# nrf91-feather.net
KiCad netlist of a schematic drawn in EAGLE
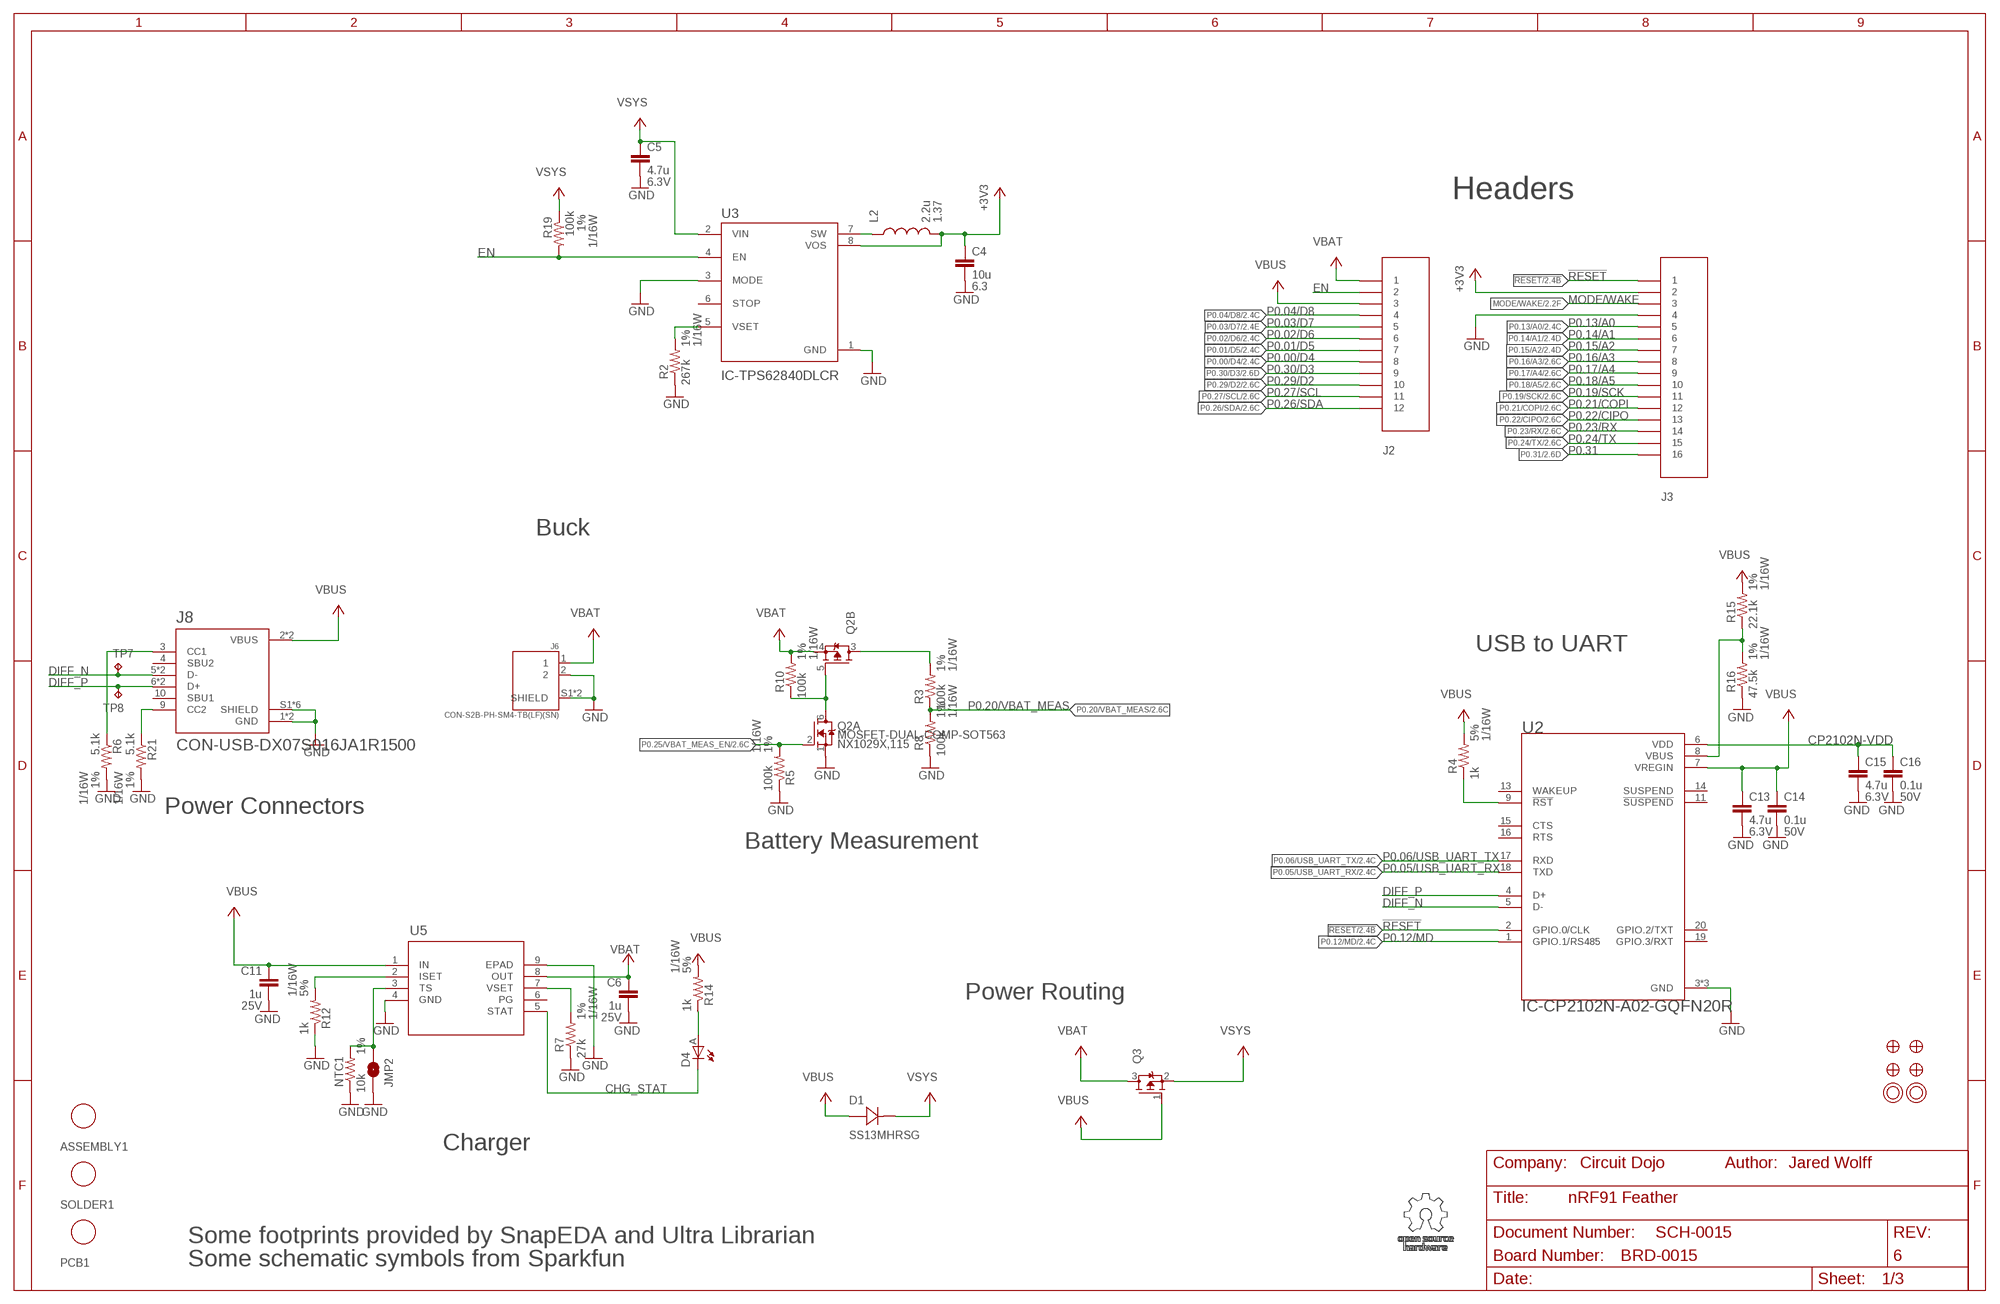
[diagram p0: schematic, sheet 1]
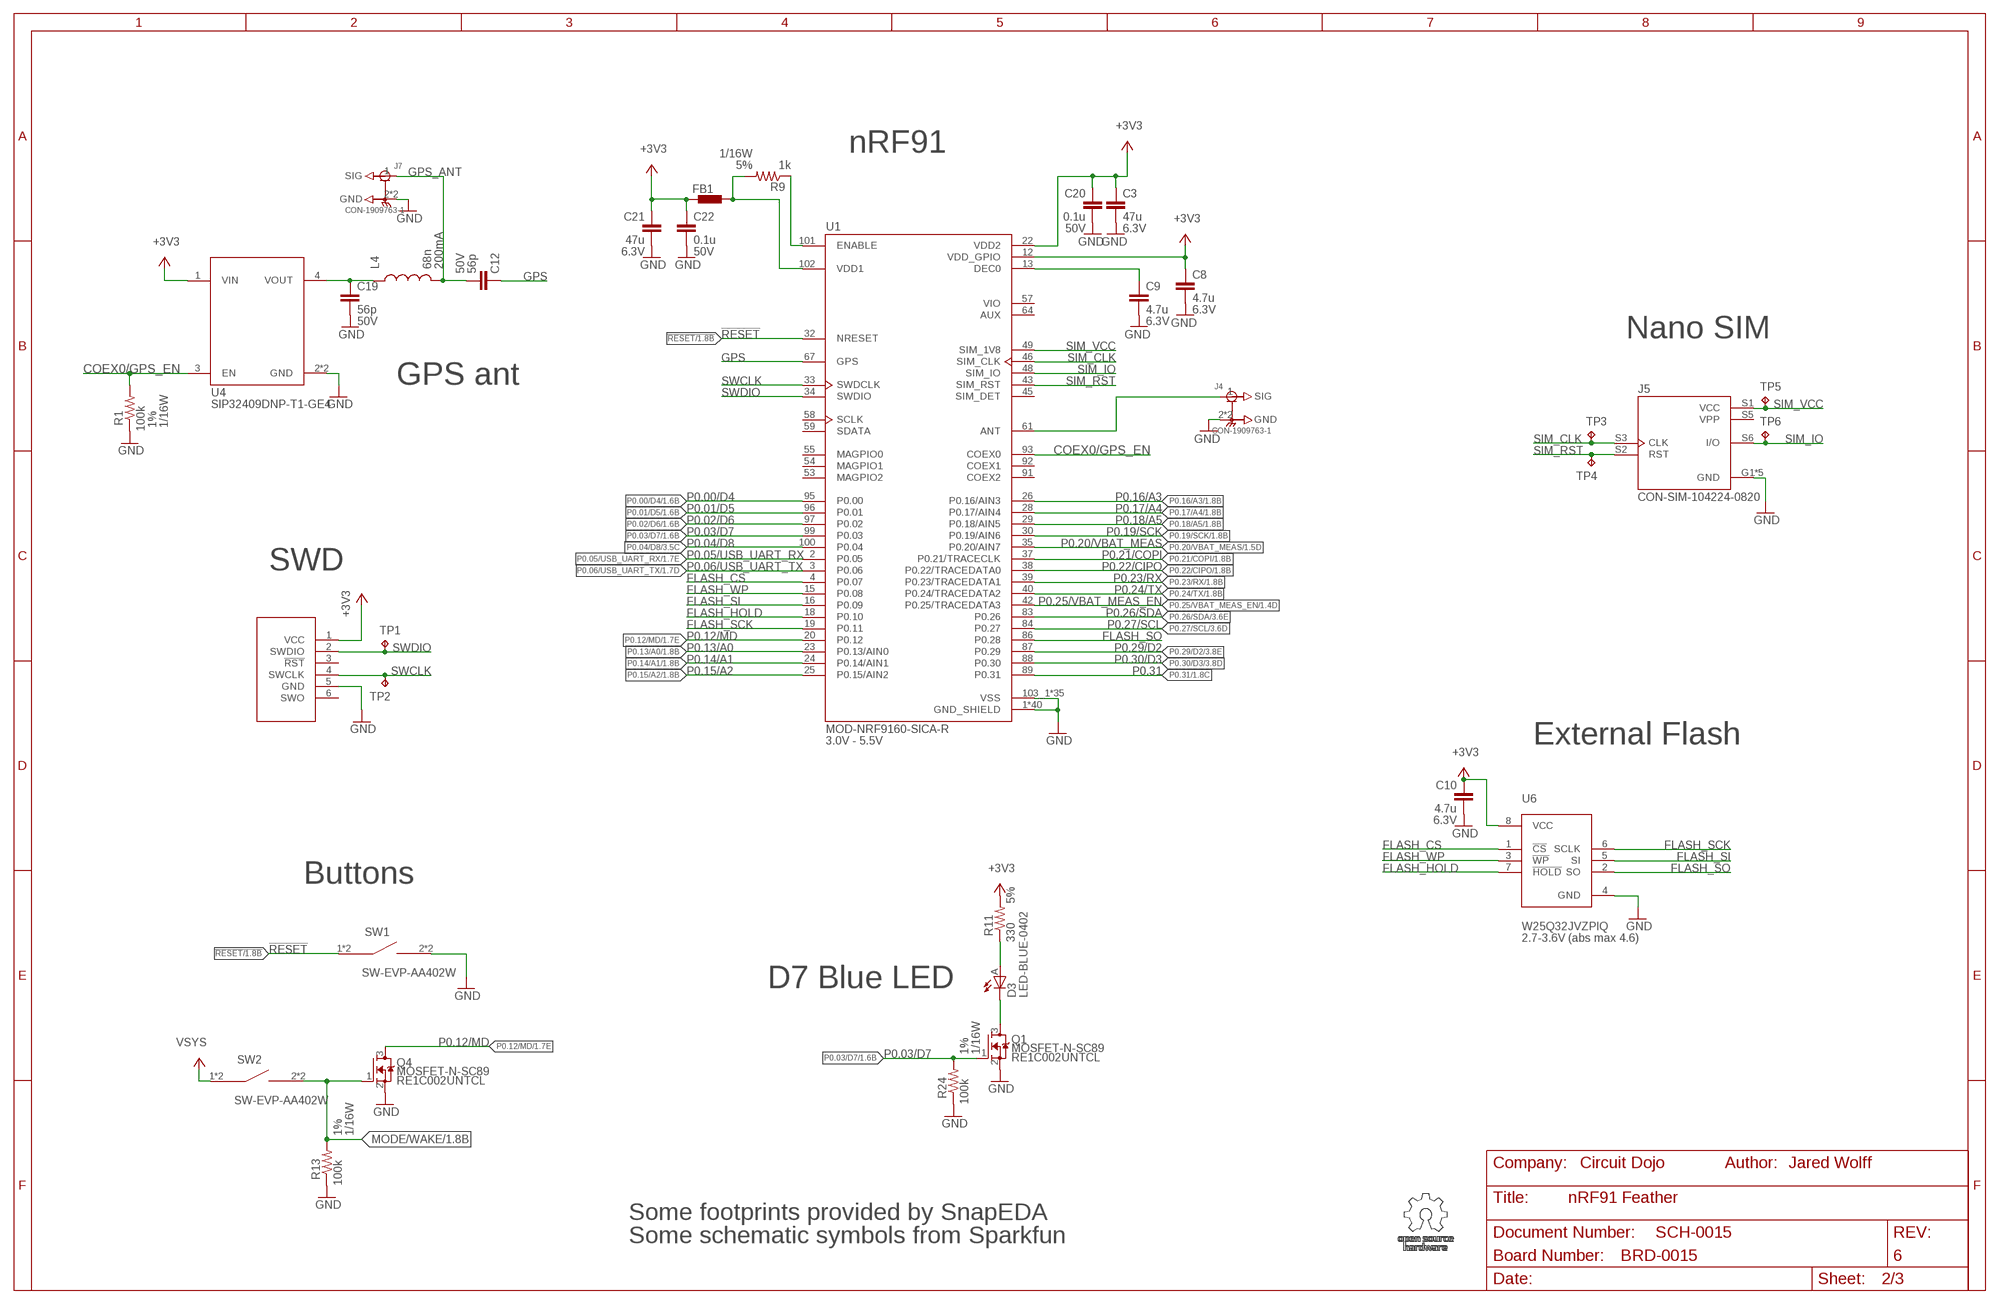
[diagram p1: schematic, sheet 2]
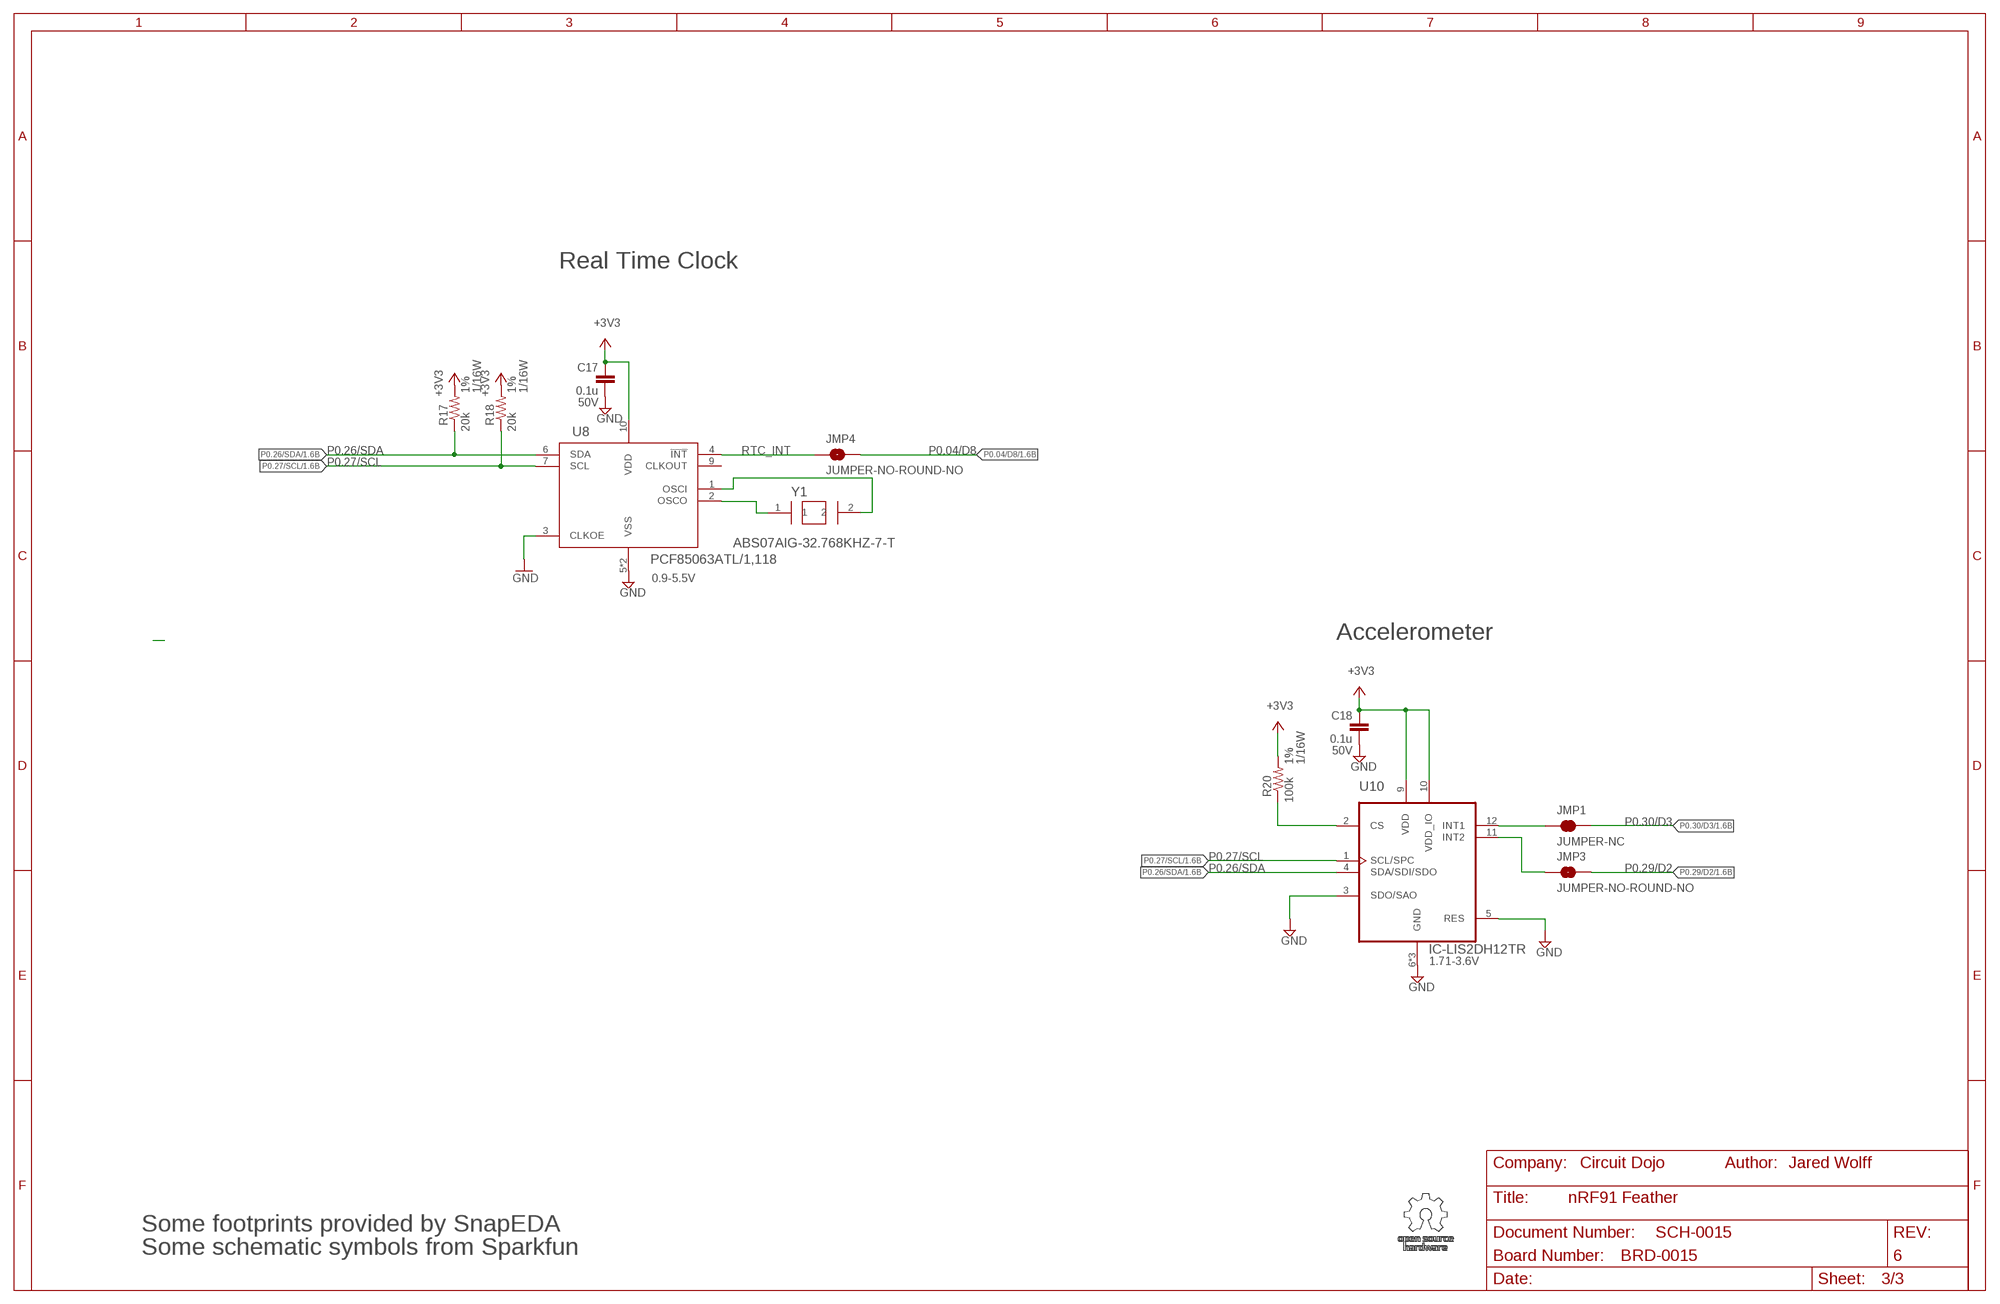
[diagram p2: schematic, sheet 3]

(export (version "E")
  (design (tool "Eeschema 10.0.6"))
  (components
    (comp (ref "ASSEMBLY1")
      (value "ASSY-COST-NRF91-FEATHER")
      (footprint "eagle-import:PLACEHOLDER")
      (fields (field (name "MPN") "ASSY-COST-NRF9160-FEATHER"))
      (libsource (lib "eagle-import") (part "ASSY-COST-NRF91-FEATHER"))
    )
    (comp (ref "C4")
      (value "10u")
      (footprint "eagle-import:C0603")
      (fields (field (name "MPN") "JMK107ABJ106MA-T") (field (name "VOLTHIGH") "6.3"))
      (libsource (lib "eagle-import") (part "CAP-0603-10U-6.3V"))
    )
    (comp (ref "C5")
      (value "4.7u")
      (footprint "eagle-import:C0603")
      (fields (field (name "MPN") "JMK107BB7475MA-T") (field (name "VOLTHIGH") "6.3V"))
      (libsource (lib "eagle-import") (part "CAP-0603-4.7U-6.3V-2"))
    )
    (comp (ref "C6")
      (value "1u")
      (footprint "eagle-import:CAPC1005X55N")
      (fields
        (field (name "MF") "TDK")
        (field (name "MPN") "C1005X5R1E105M050BC")
        (field (name "VOLTHIGH") "25V")
      )
      (libsource (lib "eagle-import") (part "CAP-0402-1U-25V-1"))
    )
    (comp (ref "C11")
      (value "1u")
      (footprint "eagle-import:CAPC1005X55N")
      (fields
        (field (name "MF") "TDK")
        (field (name "MPN") "C1005X5R1E105M050BC")
        (field (name "VOLTHIGH") "25V")
      )
      (libsource (lib "eagle-import") (part "CAP-0402-1U-25V-1"))
    )
    (comp (ref "C13")
      (value "4.7u")
      (footprint "eagle-import:C0603")
      (fields (field (name "MPN") "JMK107BB7475MA-T") (field (name "VOLTHIGH") "6.3V"))
      (libsource (lib "eagle-import") (part "CAP-0603-4.7U-6.3V-2"))
    )
    (comp (ref "C14")
      (value "0.1u")
      (footprint "eagle-import:CAPC1005X55N")
      (fields
        (field (name "MF") "Taiyo Yuden")
        (field (name "MPN") "UMK105BJ104KV-F")
        (field (name "VOLTHIGH") "50V")
      )
      (libsource (lib "eagle-import") (part "CAP-0402-0.1U-50V"))
    )
    (comp (ref "C15")
      (value "4.7u")
      (footprint "eagle-import:C0603")
      (fields (field (name "MPN") "JMK107BB7475MA-T") (field (name "VOLTHIGH") "6.3V"))
      (libsource (lib "eagle-import") (part "CAP-0603-4.7U-6.3V-2"))
    )
    (comp (ref "C16")
      (value "0.1u")
      (footprint "eagle-import:CAPC1005X55N")
      (fields
        (field (name "MF") "Taiyo Yuden")
        (field (name "MPN") "UMK105BJ104KV-F")
        (field (name "VOLTHIGH") "50V")
      )
      (libsource (lib "eagle-import") (part "CAP-0402-0.1U-50V"))
    )
    (comp (ref "D1")
      (value "DIO-SCHOTTKY-1A-SMA-MICRO")
      (footprint "eagle-import:SMA-MICRO")
      (fields (field (name "MPN") "SS13MHRSG"))
      (libsource (lib "eagle-import") (part "DIO-SCHOTTKY-SMA-MICRO-1A"))
    )
    (comp (ref "D4")
      (value "LED-ORANGE-0402")
      (footprint "eagle-import:LED_EAST1005")
      (fields (field (name "MF") "Everlight Electronics Co Ltd") (field (name "MPN") "EAST1005GA1"))
      (libsource (lib "eagle-import") (part "LED-0402-ORANGE"))
    )
    (comp (ref "J2")
      (value "CON-HEADER-1X12-MALE-PIN")
      (footprint "eagle-import:CON-HEADER-1X12-MALE-PIN")
      (libsource (lib "eagle-import") (part "CON-HEADER-1X12-MALE-PIN"))
    )
    (comp (ref "J3")
      (value "CON-HEADER-1X16-MALE-PIN")
      (footprint "eagle-import:CON-HEADER-1X16-MALE-PIN")
      (libsource (lib "eagle-import") (part "CON-HEADER-1X16-MALE-PIN"))
    )
    (comp (ref "J6")
      (value "CON-S2B-PH-SM4-TB(LF)(SN)")
      (footprint "eagle-import:JST_S2B-PH-SM4-TB(LF)(SN)")
      (fields (field (name "MF") "JST Sales") (field (name "MPN") "S2B-PH-SM4-TB(LF)(SN)"))
      (libsource (lib "eagle-import") (part "CON-S2B-PH-SM4-TB(LF)(SN)"))
    )
    (comp (ref "J8")
      (value "CON-USB-DX07S016JA1R1500")
      (footprint "eagle-import:JAE_DX07S016JA1R1500")
      (fields
        (field (name "DIGI-KEY_PART_NUMBER") "670-DX07S016JA1R1500CT-ND")
        (field (name "MF") "JAE Electronics")
        (field (name "MP") "DX07S016JA1R1500")
      )
      (libsource (lib "eagle-import") (part "CON-USB-DX07S016JA1R1500"))
    )
    (comp (ref "JMP2")
      (value "JUMPER-NO-ROUND-NO")
      (footprint "eagle-import:JUMPER-ROUND-N0")
      (libsource (lib "eagle-import") (part "JUMPER-NO-ROUND-NO"))
    )
    (comp (ref "L2")
      (value "2.2u")
      (footprint "eagle-import:IND-2P0X2P0X1P2")
      (fields (field (name "CURRENT") "1.37") (field (name "MPN") "NRS2012T2R2MGJ"))
      (libsource (lib "eagle-import") (part "IND-2.2U-1.37A-2X2"))
    )
    (comp (ref "NTC1")
      (value "10k")
      (footprint "eagle-import:R0402-M")
      (fields
        (field (name "MF") "Murata Electronics")
        (field (name "MPN") "NCU15XH103F60RC")
        (field (name "TOLERANCE") "1%")
      )
      (libsource (lib "eagle-import") (part "NTC-0402-10K-1%"))
    )
    (comp (ref "PCB1")
      (value "PCB-NRF91-FEATHER")
      (footprint "eagle-import:PLACEHOLDER")
      (fields (field (name "MPN") "BRD-0015"))
      (libsource (lib "eagle-import") (part "PCB-NRF91-FEATHER"))
    )
    (comp (ref "Q2")
      (value "MOSFET-DUAL-COMP-SOT563")
      (footprint "eagle-import:SOT50P160X60-6N")
      (fields (field (name "MPN") "NX1029X,115"))
      (libsource (lib "eagle-import") (part "MOSFET-DUAL-COMP-SOT563"))
    )
    (comp (ref "Q3")
      (value "MOSFET-P-20V-4.7A-SOT23")
      (footprint "eagle-import:SOT23")
      (fields (field (name "MPN") "TSM500P02CX RFG"))
      (libsource (lib "eagle-import") (part "MOSFET-P-SOT23-20V-4.7A"))
    )
    (comp (ref "R2")
      (value "267k")
      (footprint "eagle-import:R0402-M")
      (fields
        (field (name "MPN") "RC0402FR-07267KL")
        (field (name "POWER") "1/16W")
        (field (name "TOLERANCE") "1%")
      )
      (libsource (lib "eagle-import") (part "RES-0402-267K-1%"))
    )
    (comp (ref "R3")
      (value "100k")
      (footprint "eagle-import:R0402-M")
      (fields
        (field (name "MPN") "RC0402FR07100KL")
        (field (name "POWER") "1/16W")
        (field (name "TOLERANCE") "1%")
      )
      (libsource (lib "eagle-import") (part "RES-0402-100K-1%"))
    )
    (comp (ref "R4")
      (value "1k")
      (footprint "eagle-import:R0402-M")
      (fields
        (field (name "MPN") "RC0402JR-071KL")
        (field (name "POWER") "1/16W")
        (field (name "TOLERANCE") "5%")
      )
      (libsource (lib "eagle-import") (part "RES-0402-1K-5%"))
    )
    (comp (ref "R5")
      (value "100k")
      (footprint "eagle-import:R0402-M")
      (fields
        (field (name "MPN") "RC0402FR07100KL")
        (field (name "POWER") "1/16W")
        (field (name "TOLERANCE") "1%")
      )
      (libsource (lib "eagle-import") (part "RES-0402-100K-1%"))
    )
    (comp (ref "R6")
      (value "5.1k")
      (footprint "eagle-import:R0402-M")
      (fields
        (field (name "MPN") "RC0402FR-075K1L")
        (field (name "POWER") "1/16W")
        (field (name "TOLERANCE") "1%")
      )
      (libsource (lib "eagle-import") (part "RES-0402-5.1K-1%"))
    )
    (comp (ref "R7")
      (value "27k")
      (footprint "eagle-import:R0402-M")
      (fields (field (name "MF") "Yageo") (field (name "POWER") "1/16W") (field (name "TOLERANCE") "1%"))
      (libsource (lib "eagle-import") (part "RES-0402-27K-1%"))
    )
    (comp (ref "R8")
      (value "100k")
      (footprint "eagle-import:R0402-M")
      (fields
        (field (name "MPN") "RC0402FR07100KL")
        (field (name "POWER") "1/16W")
        (field (name "TOLERANCE") "1%")
      )
      (libsource (lib "eagle-import") (part "RES-0402-100K-1%"))
    )
    (comp (ref "R10")
      (value "100k")
      (footprint "eagle-import:R0402-M")
      (fields
        (field (name "MPN") "RC0402FR07100KL")
        (field (name "POWER") "1/16W")
        (field (name "TOLERANCE") "1%")
      )
      (libsource (lib "eagle-import") (part "RES-0402-100K-1%"))
    )
    (comp (ref "R12")
      (value "1k")
      (footprint "eagle-import:R0402-M")
      (fields
        (field (name "MPN") "RC0402JR-071KL")
        (field (name "POWER") "1/16W")
        (field (name "TOLERANCE") "5%")
      )
      (libsource (lib "eagle-import") (part "RES-0402-1K-5%"))
    )
    (comp (ref "R14")
      (value "1k")
      (footprint "eagle-import:R0402-M")
      (fields
        (field (name "MPN") "RC0402JR-071KL")
        (field (name "POWER") "1/16W")
        (field (name "TOLERANCE") "5%")
      )
      (libsource (lib "eagle-import") (part "RES-0402-1K-5%"))
    )
    (comp (ref "R15")
      (value "22.1k")
      (footprint "eagle-import:R0402-M")
      (fields
        (field (name "MF") "Yageo")
        (field (name "MPN") "RC0402FR-0722K1L")
        (field (name "POWER") "1/16W")
        (field (name "TOLERANCE") "1%")
      )
      (libsource (lib "eagle-import") (part "RES-0402-22.1K-1%"))
    )
    (comp (ref "R16")
      (value "47.5k")
      (footprint "eagle-import:R0402-M")
      (fields
        (field (name "MF") "Yageo")
        (field (name "MPN") "RC0402FR-0747K5L")
        (field (name "POWER") "1/16W")
        (field (name "TOLERANCE") "1%")
      )
      (libsource (lib "eagle-import") (part "RES-0402-47.5K-1%"))
    )
    (comp (ref "R19")
      (value "100k")
      (footprint "eagle-import:R0402-M")
      (fields
        (field (name "MPN") "RC0402FR07100KL")
        (field (name "POWER") "1/16W")
        (field (name "TOLERANCE") "1%")
      )
      (libsource (lib "eagle-import") (part "RES-0402-100K-1%"))
    )
    (comp (ref "R21")
      (value "5.1k")
      (footprint "eagle-import:R0402-M")
      (fields
        (field (name "MPN") "RC0402FR-075K1L")
        (field (name "POWER") "1/16W")
        (field (name "TOLERANCE") "1%")
      )
      (libsource (lib "eagle-import") (part "RES-0402-5.1K-1%"))
    )
    (comp (ref "SOLDER1")
      (value "SOLDER-PASTE-ROOM-TEMP-50G")
      (footprint "eagle-import:PLACEHOLDER")
      (fields (field (name "MPN") "TS391SNL50") (field (name "MQTY") "150"))
      (libsource (lib "eagle-import") (part "SOLDER-PASTE-ROOM-TEMP-50G"))
    )
    (comp (ref "TP7")
      (value "TP-1SIDE-1P0")
      (footprint "eagle-import:TP-1P0")
      (libsource (lib "eagle-import") (part "TP-1SIDE-1P0"))
    )
    (comp (ref "TP8")
      (value "TP-1SIDE-1P0")
      (footprint "eagle-import:TP-1P0")
      (libsource (lib "eagle-import") (part "TP-1SIDE-1P0"))
    )
    (comp (ref "U$3")
      (value "FIDUCIAL-1MM")
      (footprint "eagle-import:FIDUCIAL-1MM")
      (libsource (lib "eagle-import") (part "FIDUCIAL-1MM"))
    )
    (comp (ref "U$4")
      (value "FIDUCIAL-1MM")
      (footprint "eagle-import:FIDUCIAL-1MM")
      (libsource (lib "eagle-import") (part "FIDUCIAL-1MM"))
    )
    (comp (ref "U$31")
      (value "MOUNTING-HOLE-2.5MM-PLATED")
      (footprint "eagle-import:MOUNTING-HOLE-2.5MM-PLATED")
      (libsource (lib "eagle-import") (part "MOUNTING-HOLE-2.5MM-PLATED"))
    )
    (comp (ref "U$32")
      (value "MOUNTING-HOLE-2.5MM-PLATED")
      (footprint "eagle-import:MOUNTING-HOLE-2.5MM-PLATED")
      (libsource (lib "eagle-import") (part "MOUNTING-HOLE-2.5MM-PLATED"))
    )
    (comp (ref "U$34")
      (value "FIDUCIAL-1MM")
      (footprint "eagle-import:FIDUCIAL-1MM")
      (libsource (lib "eagle-import") (part "FIDUCIAL-1MM"))
    )
    (comp (ref "U$35")
      (value "FIDUCIAL-1MM")
      (footprint "eagle-import:FIDUCIAL-1MM")
      (libsource (lib "eagle-import") (part "FIDUCIAL-1MM"))
    )
    (comp (ref "U2")
      (value "IC-CP2102N-A02-GQFN20R")
      (footprint "eagle-import:SILABS_CP2102N-A02-GQFN20R")
      (fields (field (name "MPN") "CP2102N-A02-GQFN20R") (field (name "MF") "Silicon Labs"))
      (libsource (lib "eagle-import") (part "IC-CP2102N-A02-GQFN20R"))
    )
    (comp (ref "U3")
      (value "IC-TPS62840DLCR")
      (footprint "eagle-import:SON50P200X150X100-8N")
      (fields (field (name "MF") "Texas Instruments") (field (name "MP") "TPS62840DLCR"))
      (libsource (lib "eagle-import") (part "IC-TPS62840DLCR"))
    )
    (comp (ref "U5")
      (value "IC-BQ25170JDSGR-WSON8")
      (footprint "eagle-import:WSON8_BQ2517_TEX-L")
      (fields
        (field (name "MF") "Texas Instruments")
        (field (name "MPN") "BQ25170JDSGR")
        (field (name "COPYRIGHT") "Copyright (C) 2022 Ultra Librarian. All rights reserved.")
      )
      (libsource (lib "eagle-import") (part "IC-BQ25170JDSGR-WSON8"))
    )
    (comp (ref "C17")
      (value "0.1u")
      (footprint "eagle-import:CAPC1005X55N")
      (fields
        (field (name "MF") "Taiyo Yuden")
        (field (name "MPN") "UMK105BJ104KV-F")
        (field (name "VOLTHIGH") "50V")
      )
      (libsource (lib "eagle-import") (part "CAP-0402-0.1U-50V"))
    )
    (comp (ref "C18")
      (value "0.1u")
      (footprint "eagle-import:CAPC1005X55N")
      (fields
        (field (name "MF") "Taiyo Yuden")
        (field (name "MPN") "UMK105BJ104KV-F")
        (field (name "VOLTHIGH") "50V")
      )
      (libsource (lib "eagle-import") (part "CAP-0402-0.1U-50V"))
    )
    (comp (ref "JMP1")
      (value "JUMPER-NC")
      (footprint "eagle-import:JUMPER-ROUND-NC")
      (libsource (lib "eagle-import") (part "JUMPER-NC"))
    )
    (comp (ref "JMP3")
      (value "JUMPER-NO-ROUND-NO")
      (footprint "eagle-import:JUMPER-ROUND-N0")
      (libsource (lib "eagle-import") (part "JUMPER-NO-ROUND-NO"))
    )
    (comp (ref "JMP4")
      (value "JUMPER-NO-ROUND-NO")
      (footprint "eagle-import:JUMPER-ROUND-N0")
      (libsource (lib "eagle-import") (part "JUMPER-NO-ROUND-NO"))
    )
    (comp (ref "R17")
      (value "20k")
      (footprint "eagle-import:R0402-M")
      (fields
        (field (name "MF") "Yageo")
        (field (name "MPN") "RC0402FR-0720KL")
        (field (name "POWER") "1/16W")
        (field (name "TOLERANCE") "1%")
      )
      (libsource (lib "eagle-import") (part "RES-0402-20K-1%"))
    )
    (comp (ref "R18")
      (value "20k")
      (footprint "eagle-import:R0402-M")
      (fields
        (field (name "MF") "Yageo")
        (field (name "MPN") "RC0402FR-0720KL")
        (field (name "POWER") "1/16W")
        (field (name "TOLERANCE") "1%")
      )
      (libsource (lib "eagle-import") (part "RES-0402-20K-1%"))
    )
    (comp (ref "R20")
      (value "100k")
      (footprint "eagle-import:R0402-M")
      (fields
        (field (name "MPN") "RC0402FR07100KL")
        (field (name "POWER") "1/16W")
        (field (name "TOLERANCE") "1%")
      )
      (libsource (lib "eagle-import") (part "RES-0402-100K-1%"))
    )
    (comp (ref "U8")
      (value "IC-PCF85063ATL/1")
      (footprint "eagle-import:DFN10_2P7X2P7-L")
      (fields (field (name "MPN") "PCF85063ATL/1,118") (field (name "MF") "NXP"))
      (libsource (lib "eagle-import") (part "IC-PCF85063ATL/1"))
    )
    (comp (ref "U10")
      (value "IC-LIS2DH12TR")
      (footprint "eagle-import:PQFN50P200X200100-12N")
      (fields (field (name "MF") "STMicroelectronics") (field (name "MPN") "LIS2DH12TR"))
      (libsource (lib "eagle-import") (part "IC-LIS2DH12TR"))
    )
    (comp (ref "Y1")
      (value "XTAL-ABS07AIG-32.768KHZ-7-T")
      (footprint "eagle-import:XTAL320X150X90")
      (fields (field (name "MPN") "ABS07AIG-32.768KHZ-7-T") (field (name "MF") "Abracon"))
      (libsource (lib "eagle-import") (part "XTAL-ABS07AIG-32.768KHZ-7-T"))
    )
    (comp (ref "C3")
      (value "47u")
      (footprint "eagle-import:C0805")
      (fields (field (name "MPN") "JMK212BJ476MG-T") (field (name "VOLTHIGH") "6.3V"))
      (libsource (lib "eagle-import") (part "CAP-0805-47U-6.3V"))
    )
    (comp (ref "C8")
      (value "4.7u")
      (footprint "eagle-import:C0603")
      (fields (field (name "MPN") "JMK107BB7475MA-T") (field (name "VOLTHIGH") "6.3V"))
      (libsource (lib "eagle-import") (part "CAP-0603-4.7U-6.3V-2"))
    )
    (comp (ref "C9")
      (value "4.7u")
      (footprint "eagle-import:C0603")
      (fields (field (name "MPN") "JMK107BB7475MA-T") (field (name "VOLTHIGH") "6.3V"))
      (libsource (lib "eagle-import") (part "CAP-0603-4.7U-6.3V-2"))
    )
    (comp (ref "C10")
      (value "4.7u")
      (footprint "eagle-import:C0603")
      (fields (field (name "MPN") "JMK107BB7475MA-T") (field (name "VOLTHIGH") "6.3V"))
      (libsource (lib "eagle-import") (part "CAP-0603-4.7U-6.3V-2"))
    )
    (comp (ref "C12")
      (value "56p")
      (footprint "eagle-import:CAPC1005X55N")
      (fields
        (field (name "MF") "Yageo")
        (field (name "MPN") "CC0402GRNPO9BN560")
        (field (name "VOLTHIGH") "50V")
      )
      (libsource (lib "eagle-import") (part "CAP-0402-56PF-50V-1"))
    )
    (comp (ref "C19")
      (value "56p")
      (footprint "eagle-import:CAPC1005X55N")
      (fields
        (field (name "MF") "Yageo")
        (field (name "MPN") "CC0402GRNPO9BN560")
        (field (name "VOLTHIGH") "50V")
      )
      (libsource (lib "eagle-import") (part "CAP-0402-56PF-50V-1"))
    )
    (comp (ref "C20")
      (value "0.1u")
      (footprint "eagle-import:CAPC1005X55N")
      (fields
        (field (name "MF") "Taiyo Yuden")
        (field (name "MPN") "UMK105BJ104KV-F")
        (field (name "VOLTHIGH") "50V")
      )
      (libsource (lib "eagle-import") (part "CAP-0402-0.1U-50V"))
    )
    (comp (ref "C21")
      (value "47u")
      (footprint "eagle-import:C0805")
      (fields (field (name "MPN") "JMK212BJ476MG-T") (field (name "VOLTHIGH") "6.3V"))
      (libsource (lib "eagle-import") (part "CAP-0805-47U-6.3V"))
    )
    (comp (ref "C22")
      (value "0.1u")
      (footprint "eagle-import:CAPC1005X55N")
      (fields
        (field (name "MF") "Taiyo Yuden")
        (field (name "MPN") "UMK105BJ104KV-F")
        (field (name "VOLTHIGH") "50V")
      )
      (libsource (lib "eagle-import") (part "CAP-0402-0.1U-50V"))
    )
    (comp (ref "D3")
      (value "LED-BLUE-0402")
      (footprint "eagle-import:LED_EAST1005")
      (fields (field (name "MF") "Everlight Electronics Co Ltd") (field (name "MPN") "EAST10052BA0"))
      (libsource (lib "eagle-import") (part "LED-0402-BLUE"))
    )
    (comp (ref "FB1")
      (value "FERRITE-120-100MHZ-0402")
      (footprint "eagle-import:R0402-M")
      (fields (field (name "MF") "Murata Electronics") (field (name "MPN") "BLM15AX121SN1D"))
      (libsource (lib "eagle-import") (part "FERRITE-0402-120-100MHZ"))
    )
    (comp (ref "J4")
      (value "CON-1909763-1")
      (footprint "eagle-import:TE_1909763-1")
      (fields (field (name "MF") "TE Connectivity") (field (name "MPN") "1909763-1"))
      (libsource (lib "eagle-import") (part "CON-1909763-1"))
    )
    (comp (ref "J5")
      (value "CON-SIM-104224-0820")
      (footprint "eagle-import:MOLEX_104224-0820")
      (fields (field (name "MF") "Molex") (field (name "MPN") "104224-0820"))
      (libsource (lib "eagle-import") (part "CON-SIM-104224-0820"))
    )
    (comp (ref "J7")
      (value "CON-1909763-1")
      (footprint "eagle-import:TE_1909763-1")
      (fields (field (name "MF") "TE Connectivity") (field (name "MPN") "1909763-1"))
      (libsource (lib "eagle-import") (part "CON-1909763-1"))
    )
    (comp (ref "J9")
      (value "CON-TC2030-MCP-NL")
      (footprint "eagle-import:TC2030-MCP-NL")
      (fields (field (name "MPN") "TC2030-MCP-NL"))
      (libsource (lib "eagle-import") (part "CON-TC2030-MCP-NL"))
    )
    (comp (ref "L4")
      (value "68n")
      (footprint "eagle-import:IND0402_22N_TAI")
      (fields (field (name "CURRENT") "200mA") (field (name "MPN") "LQG15HN68NH02D‎"))
      (libsource (lib "eagle-import") (part "IND-0402-68NH-200MA"))
    )
    (comp (ref "Q1")
      (value "MOSFET-N-SC89")
      (footprint "eagle-import:DIO_RB558WMF-L")
      (fields (field (name "MPN") "RE1C002UNTCL") (field (name "MF") "Rohm Semiconductor"))
      (libsource (lib "eagle-import") (part "MOSFET-N-SC89"))
    )
    (comp (ref "Q4")
      (value "MOSFET-N-SC89")
      (footprint "eagle-import:DIO_RB558WMF-L")
      (fields (field (name "MPN") "RE1C002UNTCL") (field (name "MF") "Rohm Semiconductor"))
      (libsource (lib "eagle-import") (part "MOSFET-N-SC89"))
    )
    (comp (ref "R1")
      (value "100k")
      (footprint "eagle-import:R0402-M")
      (fields
        (field (name "MPN") "RC0402FR07100KL")
        (field (name "POWER") "1/16W")
        (field (name "TOLERANCE") "1%")
      )
      (libsource (lib "eagle-import") (part "RES-0402-100K-1%"))
    )
    (comp (ref "R9")
      (value "1k")
      (footprint "eagle-import:R0402-M")
      (fields
        (field (name "MPN") "RC0402JR-071KL")
        (field (name "POWER") "1/16W")
        (field (name "TOLERANCE") "5%")
      )
      (libsource (lib "eagle-import") (part "RES-0402-1K-5%"))
    )
    (comp (ref "R11")
      (value "330")
      (footprint "eagle-import:R0402-M")
      (fields
        (field (name "MF") "Yageo")
        (field (name "MPN") "RC0402JR-07330RL")
        (field (name "TOLERANCE") "5%")
      )
      (libsource (lib "eagle-import") (part "RES-0402-330-5%"))
    )
    (comp (ref "R13")
      (value "100k")
      (footprint "eagle-import:R0402-M")
      (fields
        (field (name "MPN") "RC0402FR07100KL")
        (field (name "POWER") "1/16W")
        (field (name "TOLERANCE") "1%")
      )
      (libsource (lib "eagle-import") (part "RES-0402-100K-1%"))
    )
    (comp (ref "R24")
      (value "100k")
      (footprint "eagle-import:R0402-M")
      (fields
        (field (name "MPN") "RC0402FR07100KL")
        (field (name "POWER") "1/16W")
        (field (name "TOLERANCE") "1%")
      )
      (libsource (lib "eagle-import") (part "RES-0402-100K-1%"))
    )
    (comp (ref "SW1")
      (value "SW-EVP-AA402W")
      (footprint "eagle-import:SW-EVP-AA402W")
      (fields (field (name "MPN") "EVP-AA402W"))
      (libsource (lib "eagle-import") (part "SW-EVP-AA402W"))
    )
    (comp (ref "SW2")
      (value "SW-EVP-AA402W")
      (footprint "eagle-import:SW-EVP-AA402W")
      (fields (field (name "MPN") "EVP-AA402W"))
      (libsource (lib "eagle-import") (part "SW-EVP-AA402W"))
    )
    (comp (ref "TP1")
      (value "TP-1SIDE-1P0")
      (footprint "eagle-import:TP-1P0")
      (libsource (lib "eagle-import") (part "TP-1SIDE-1P0"))
    )
    (comp (ref "TP2")
      (value "TP-1SIDE-1P0")
      (footprint "eagle-import:TP-1P0")
      (libsource (lib "eagle-import") (part "TP-1SIDE-1P0"))
    )
    (comp (ref "TP3")
      (value "TP-1SIDE-1P0")
      (footprint "eagle-import:TP-1P0")
      (libsource (lib "eagle-import") (part "TP-1SIDE-1P0"))
    )
    (comp (ref "TP4")
      (value "TP-1SIDE-1P0")
      (footprint "eagle-import:TP-1P0")
      (libsource (lib "eagle-import") (part "TP-1SIDE-1P0"))
    )
    (comp (ref "TP5")
      (value "TP-1SIDE-1P0")
      (footprint "eagle-import:TP-1P0")
      (libsource (lib "eagle-import") (part "TP-1SIDE-1P0"))
    )
    (comp (ref "TP6")
      (value "TP-1SIDE-1P0")
      (footprint "eagle-import:TP-1P0")
      (libsource (lib "eagle-import") (part "TP-1SIDE-1P0"))
    )
    (comp (ref "U1")
      (value "MOD-NRF9160-SICA-R")
      (footprint "eagle-import:NORDIC_NRF9160-SICA-R")
      (fields (field (name "MF") "Nordic Semiconductor") (field (name "MPN") "NRF9160-SICA-R"))
      (libsource (lib "eagle-import") (part "MOD-NRF9160-SICA-R"))
    )
    (comp (ref "U4")
      (value "POWER-SWITCH-SIP32409-DFN4")
      (footprint "eagle-import:SON50P160X120X60-5N")
      (fields (field (name "MF") "Vishay Siliconix") (field (name "MPN") "SIP32409DNP-T1-GE4"))
      (libsource (lib "eagle-import") (part "POWER-SWITCH-DFN4-SIP32409"))
    )
    (comp (ref "U6")
      (value "FLASH-W25Q32JVZPIQ-WSON")
      (footprint "eagle-import:WIN_ZP-8-L")
      (fields (field (name "MPN") "W25Q32JVZPIQ"))
      (libsource (lib "eagle-import") (part "FLASH-WSON-W25Q32JVZPIQ"))
    )
  )
  (nets
    (net (code "1") (name "+3V3") (class "Default")
      (node (ref "C10") (pin "1") (pinfunction "1_1") (pintype "passive"))
      (node (ref "C17") (pin "1") (pinfunction "1_1") (pintype "passive"))
      (node (ref "C18") (pin "1") (pinfunction "1_1") (pintype "passive"))
      (node (ref "C20") (pin "1") (pinfunction "1_1") (pintype "passive"))
      (node (ref "C21") (pin "1") (pinfunction "1_1") (pintype "passive"))
      (node (ref "C22") (pin "1") (pinfunction "1_1") (pintype "passive"))
      (node (ref "C3") (pin "1") (pinfunction "1_1") (pintype "passive"))
      (node (ref "C4") (pin "1") (pinfunction "1_1") (pintype "passive"))
      (node (ref "C8") (pin "1") (pinfunction "1_1") (pintype "passive"))
      (node (ref "FB1") (pin "1") (pinfunction "1_1") (pintype "passive"))
      (node (ref "J3") (pin "2") (pinfunction "2_2") (pintype "bidirectional"))
      (node (ref "J9") (pin "1") (pinfunction "VCC_1") (pintype "bidirectional"))
      (node (ref "L2") (pin "P$2") (pinfunction "2_P$2") (pintype "passive"))
      (node (ref "R11") (pin "2") (pinfunction "2_2") (pintype "passive"))
      (node (ref "R17") (pin "2") (pinfunction "2_2") (pintype "passive"))
      (node (ref "R18") (pin "2") (pinfunction "2_2") (pintype "passive"))
      (node (ref "R20") (pin "2") (pinfunction "2_2") (pintype "passive"))
      (node (ref "U1") (pin "12") (pinfunction "VDD_GPIO_12") (pintype "power_in"))
      (node (ref "U1") (pin "22") (pinfunction "VDD2_22") (pintype "power_in"))
      (node (ref "U10") (pin "10") (pinfunction "VDD_IO_10") (pintype "power_in"))
      (node (ref "U10") (pin "9") (pinfunction "VDD_9") (pintype "power_in"))
      (node (ref "U3") (pin "8") (pinfunction "VOS_8") (pintype "input"))
      (node (ref "U4") (pin "1") (pinfunction "VIN_1") (pintype "power_in"))
      (node (ref "U6") (pin "8") (pinfunction "VCC_8") (pintype "bidirectional"))
      (node (ref "U8") (pin "10") (pinfunction "VDD_10") (pintype "power_in"))
    )
    (net (code "2") (name "CHG_STAT") (class "Default")
      (node (ref "D4") (pin "C") (pinfunction "C_C") (pintype "passive"))
      (node (ref "U5") (pin "5") (pinfunction "STAT_5") (pintype "output"))
    )
    (net (code "3") (name "COEX0{slash}GPS_EN") (class "Default")
      (node (ref "R1") (pin "2") (pinfunction "2_2") (pintype "passive"))
      (node (ref "U1") (pin "93") (pinfunction "COEX0_93") (pintype "bidirectional"))
      (node (ref "U4") (pin "3") (pinfunction "EN_3") (pintype "input"))
    )
    (net (code "4") (name "CP2102N-VDD") (class "Default")
      (node (ref "C15") (pin "1") (pinfunction "1_1") (pintype "passive"))
      (node (ref "C16") (pin "1") (pinfunction "1_1") (pintype "passive"))
      (node (ref "U2") (pin "6") (pinfunction "VDD_6") (pintype "power_in"))
    )
    (net (code "5") (name "DIFF_N") (class "Default")
      (node (ref "J8") (pin "5") (pinfunction "D-_5") (pintype "passive"))
      (node (ref "J8") (pin "8") (pinfunction "D-_8") (pintype "passive"))
      (node (ref "TP7") (pin "TP") (pinfunction "TP_TP") (pintype "input"))
      (node (ref "U2") (pin "5") (pinfunction "D-_5") (pintype "bidirectional"))
    )
    (net (code "6") (name "DIFF_P") (class "Default")
      (node (ref "J8") (pin "6") (pinfunction "D+_6") (pintype "passive"))
      (node (ref "J8") (pin "7") (pinfunction "D+_7") (pintype "passive"))
      (node (ref "TP8") (pin "TP") (pinfunction "TP_TP") (pintype "input"))
      (node (ref "U2") (pin "4") (pinfunction "D+_4") (pintype "bidirectional"))
    )
    (net (code "7") (name "EN") (class "Default")
      (node (ref "J2") (pin "2") (pinfunction "2_2") (pintype "bidirectional"))
      (node (ref "R19") (pin "2") (pinfunction "2_2") (pintype "passive"))
      (node (ref "U3") (pin "4") (pinfunction "EN_4") (pintype "input"))
    )
    (net (code "8") (name "FLASH_CS") (class "Default")
      (node (ref "U1") (pin "4") (pinfunction "P0.07_4") (pintype "bidirectional"))
      (node (ref "U6") (pin "1") (pinfunction "~{CS}_1") (pintype "bidirectional"))
    )
    (net (code "9") (name "FLASH_HOLD") (class "Default")
      (node (ref "U1") (pin "18") (pinfunction "P0.10_18") (pintype "bidirectional"))
      (node (ref "U6") (pin "7") (pinfunction "~{HOLD}_7") (pintype "bidirectional"))
    )
    (net (code "10") (name "FLASH_SCK") (class "Default")
      (node (ref "U1") (pin "19") (pinfunction "P0.11_19") (pintype "bidirectional"))
      (node (ref "U6") (pin "6") (pinfunction "SCLK_6") (pintype "bidirectional"))
    )
    (net (code "11") (name "FLASH_SI") (class "Default")
      (node (ref "U1") (pin "16") (pinfunction "P0.09_16") (pintype "bidirectional"))
      (node (ref "U6") (pin "5") (pinfunction "SI_5") (pintype "bidirectional"))
    )
    (net (code "12") (name "FLASH_SO") (class "Default")
      (node (ref "U1") (pin "86") (pinfunction "P0.28_86") (pintype "bidirectional"))
      (node (ref "U6") (pin "2") (pinfunction "SO_2") (pintype "bidirectional"))
    )
    (net (code "13") (name "FLASH_WP") (class "Default")
      (node (ref "U1") (pin "15") (pinfunction "P0.08_15") (pintype "bidirectional"))
      (node (ref "U6") (pin "3") (pinfunction "~{WP}_3") (pintype "bidirectional"))
    )
    (net (code "14") (name "GND") (class "Default")
      (node (ref "C10") (pin "2") (pinfunction "2_2") (pintype "passive"))
      (node (ref "C11") (pin "2") (pinfunction "2_2") (pintype "passive"))
      (node (ref "C13") (pin "2") (pinfunction "2_2") (pintype "passive"))
      (node (ref "C14") (pin "2") (pinfunction "2_2") (pintype "passive"))
      (node (ref "C15") (pin "2") (pinfunction "2_2") (pintype "passive"))
      (node (ref "C16") (pin "2") (pinfunction "2_2") (pintype "passive"))
      (node (ref "C17") (pin "2") (pinfunction "2_2") (pintype "passive"))
      (node (ref "C18") (pin "2") (pinfunction "2_2") (pintype "passive"))
      (node (ref "C19") (pin "2") (pinfunction "2_2") (pintype "passive"))
      (node (ref "C20") (pin "2") (pinfunction "2_2") (pintype "passive"))
      (node (ref "C21") (pin "2") (pinfunction "2_2") (pintype "passive"))
      (node (ref "C22") (pin "2") (pinfunction "2_2") (pintype "passive"))
      (node (ref "C3") (pin "2") (pinfunction "2_2") (pintype "passive"))
      (node (ref "C4") (pin "2") (pinfunction "2_2") (pintype "passive"))
      (node (ref "C5") (pin "2") (pinfunction "2_2") (pintype "passive"))
      (node (ref "C6") (pin "2") (pinfunction "2_2") (pintype "passive"))
      (node (ref "C8") (pin "2") (pinfunction "2_2") (pintype "passive"))
      (node (ref "C9") (pin "2") (pinfunction "2_2") (pintype "passive"))
      (node (ref "J3") (pin "4") (pinfunction "4_4") (pintype "bidirectional"))
      (node (ref "J4") (pin "2") (pinfunction "GND_2") (pintype "passive"))
      (node (ref "J4") (pin "3") (pinfunction "GND_3") (pintype "passive"))
      (node (ref "J5") (pin "G1") (pinfunction "GND_G1") (pintype "power_in"))
      (node (ref "J5") (pin "G2") (pinfunction "GND_G2") (pintype "power_in"))
      (node (ref "J5") (pin "G3") (pinfunction "GND_G3") (pintype "power_in"))
      (node (ref "J5") (pin "G4") (pinfunction "GND_G4") (pintype "power_in"))
      (node (ref "J5") (pin "S4") (pinfunction "GND_S4") (pintype "power_in"))
      (node (ref "J6") (pin "2") (pinfunction "2_2") (pintype "passive"))
      (node (ref "J6") (pin "S1") (pinfunction "SHIELD_S1") (pintype "passive"))
      (node (ref "J6") (pin "S2") (pinfunction "SHIELD_S2") (pintype "passive"))
      (node (ref "J7") (pin "2") (pinfunction "GND_2") (pintype "passive"))
      (node (ref "J7") (pin "3") (pinfunction "GND_3") (pintype "passive"))
      (node (ref "J8") (pin "1") (pinfunction "GND_1") (pintype "power_in"))
      (node (ref "J8") (pin "12") (pinfunction "GND_12") (pintype "power_in"))
      (node (ref "J8") (pin "S1") (pinfunction "SHIELD_S1") (pintype "passive"))
      (node (ref "J8") (pin "S2") (pinfunction "SHIELD_S2") (pintype "passive"))
      (node (ref "J8") (pin "S3") (pinfunction "SHIELD_S3") (pintype "passive"))
      (node (ref "J8") (pin "S4") (pinfunction "SHIELD_S4") (pintype "passive"))
      (node (ref "J8") (pin "S5") (pinfunction "SHIELD_S5") (pintype "passive"))
      (node (ref "J8") (pin "S6") (pinfunction "SHIELD_S6") (pintype "passive"))
      (node (ref "J9") (pin "5") (pinfunction "GND_5") (pintype "bidirectional"))
      (node (ref "JMP2") (pin "P$2") (pinfunction "2_P$2") (pintype "passive"))
      (node (ref "NTC1") (pin "1") (pinfunction "1_1") (pintype "passive"))
      (node (ref "Q1") (pin "2") (pinfunction "S_2") (pintype "bidirectional"))
      (node (ref "Q2") (pin "1") (pinfunction "S_1") (pintype "bidirectional"))
      (node (ref "Q4") (pin "2") (pinfunction "S_2") (pintype "bidirectional"))
      (node (ref "R1") (pin "1") (pinfunction "1_1") (pintype "passive"))
      (node (ref "R12") (pin "1") (pinfunction "1_1") (pintype "passive"))
      (node (ref "R13") (pin "1") (pinfunction "1_1") (pintype "passive"))
      (node (ref "R16") (pin "1") (pinfunction "1_1") (pintype "passive"))
      (node (ref "R2") (pin "1") (pinfunction "1_1") (pintype "passive"))
      (node (ref "R21") (pin "2") (pinfunction "2_2") (pintype "passive"))
      (node (ref "R24") (pin "1") (pinfunction "1_1") (pintype "passive"))
      (node (ref "R5") (pin "1") (pinfunction "1_1") (pintype "passive"))
      (node (ref "R6") (pin "2") (pinfunction "2_2") (pintype "passive"))
      (node (ref "R7") (pin "1") (pinfunction "1_1") (pintype "passive"))
      (node (ref "R8") (pin "1") (pinfunction "1_1") (pintype "passive"))
      (node (ref "SW1") (pin "2") (pinfunction "2_2") (pintype "passive"))
      (node (ref "SW1") (pin "4") (pinfunction "2_4") (pintype "passive"))
      (node (ref "U1") (pin "1") (pinfunction "GND_SHIELD_1") (pintype "power_in"))
      (node (ref "U1") (pin "103_1") (pinfunction "VSS_103_1") (pintype "power_in"))
      (node (ref "U1") (pin "103_10") (pinfunction "VSS_103_10") (pintype "power_in"))
      (node (ref "U1") (pin "103_11") (pinfunction "VSS_103_11") (pintype "power_in"))
      (node (ref "U1") (pin "103_12") (pinfunction "VSS_103_12") (pintype "power_in"))
      (node (ref "U1") (pin "103_13") (pinfunction "VSS_103_13") (pintype "power_in"))
      (node (ref "U1") (pin "103_14") (pinfunction "VSS_103_14") (pintype "power_in"))
      (node (ref "U1") (pin "103_15") (pinfunction "VSS_103_15") (pintype "power_in"))
      (node (ref "U1") (pin "103_16") (pinfunction "VSS_103_16") (pintype "power_in"))
      (node (ref "U1") (pin "103_17") (pinfunction "VSS_103_17") (pintype "power_in"))
      (node (ref "U1") (pin "103_18") (pinfunction "VSS_103_18") (pintype "power_in"))
      (node (ref "U1") (pin "103_19") (pinfunction "VSS_103_19") (pintype "power_in"))
      (node (ref "U1") (pin "103_2") (pinfunction "VSS_103_2") (pintype "power_in"))
      (node (ref "U1") (pin "103_20") (pinfunction "VSS_103_20") (pintype "power_in"))
      (node (ref "U1") (pin "103_21") (pinfunction "VSS_103_21") (pintype "power_in"))
      (node (ref "U1") (pin "103_22") (pinfunction "VSS_103_22") (pintype "power_in"))
      (node (ref "U1") (pin "103_23") (pinfunction "VSS_103_23") (pintype "power_in"))
      (node (ref "U1") (pin "103_24") (pinfunction "VSS_103_24") (pintype "power_in"))
      (node (ref "U1") (pin "103_25") (pinfunction "VSS_103_25") (pintype "power_in"))
      (node (ref "U1") (pin "103_26") (pinfunction "VSS_103_26") (pintype "power_in"))
      (node (ref "U1") (pin "103_27") (pinfunction "VSS_103_27") (pintype "power_in"))
      (node (ref "U1") (pin "103_28") (pinfunction "VSS_103_28") (pintype "power_in"))
      (node (ref "U1") (pin "103_29") (pinfunction "VSS_103_29") (pintype "power_in"))
      (node (ref "U1") (pin "103_3") (pinfunction "VSS_103_3") (pintype "power_in"))
      (node (ref "U1") (pin "103_30") (pinfunction "VSS_103_30") (pintype "power_in"))
      (node (ref "U1") (pin "103_31") (pinfunction "VSS_103_31") (pintype "power_in"))
      (node (ref "U1") (pin "103_32") (pinfunction "VSS_103_32") (pintype "power_in"))
      (node (ref "U1") (pin "103_33") (pinfunction "VSS_103_33") (pintype "power_in"))
      (node (ref "U1") (pin "103_34") (pinfunction "VSS_103_34") (pintype "power_in"))
      (node (ref "U1") (pin "103_35") (pinfunction "VSS_103_35") (pintype "power_in"))
      (node (ref "U1") (pin "103_4") (pinfunction "VSS_103_4") (pintype "power_in"))
      (node (ref "U1") (pin "103_5") (pinfunction "VSS_103_5") (pintype "power_in"))
      (node (ref "U1") (pin "103_6") (pinfunction "VSS_103_6") (pintype "power_in"))
      (node (ref "U1") (pin "103_7") (pinfunction "VSS_103_7") (pintype "power_in"))
      (node (ref "U1") (pin "103_8") (pinfunction "VSS_103_8") (pintype "power_in"))
      (node (ref "U1") (pin "103_9") (pinfunction "VSS_103_9") (pintype "power_in"))
      (node (ref "U1") (pin "11") (pinfunction "GND_SHIELD_11") (pintype "power_in"))
      (node (ref "U1") (pin "14") (pinfunction "GND_SHIELD_14") (pintype "power_in"))
      (node (ref "U1") (pin "17") (pinfunction "GND_SHIELD_17") (pintype "power_in"))
      (node (ref "U1") (pin "21") (pinfunction "GND_SHIELD_21") (pintype "power_in"))
      (node (ref "U1") (pin "27") (pinfunction "GND_SHIELD_27") (pintype "power_in"))
      (node (ref "U1") (pin "31") (pinfunction "GND_SHIELD_31") (pintype "power_in"))
      (node (ref "U1") (pin "36") (pinfunction "GND_SHIELD_36") (pintype "power_in"))
      (node (ref "U1") (pin "41") (pinfunction "GND_SHIELD_41") (pintype "power_in"))
      (node (ref "U1") (pin "44") (pinfunction "GND_SHIELD_44") (pintype "power_in"))
      (node (ref "U1") (pin "47") (pinfunction "GND_SHIELD_47") (pintype "power_in"))
      (node (ref "U1") (pin "5") (pinfunction "GND_SHIELD_5") (pintype "power_in"))
      (node (ref "U1") (pin "50") (pinfunction "GND_SHIELD_50") (pintype "power_in"))
      (node (ref "U1") (pin "52") (pinfunction "GND_SHIELD_52") (pintype "power_in"))
      (node (ref "U1") (pin "56") (pinfunction "GND_SHIELD_56") (pintype "power_in"))
      (node (ref "U1") (pin "6") (pinfunction "GND_SHIELD_6") (pintype "power_in"))
      (node (ref "U1") (pin "60") (pinfunction "GND_SHIELD_60") (pintype "power_in"))
      (node (ref "U1") (pin "62") (pinfunction "GND_SHIELD_62") (pintype "power_in"))
      (node (ref "U1") (pin "63") (pinfunction "GND_SHIELD_63") (pintype "power_in"))
      (node (ref "U1") (pin "65") (pinfunction "GND_SHIELD_65") (pintype "power_in"))
      (node (ref "U1") (pin "66") (pinfunction "GND_SHIELD_66") (pintype "power_in"))
      (node (ref "U1") (pin "68") (pinfunction "GND_SHIELD_68") (pintype "power_in"))
      (node (ref "U1") (pin "69") (pinfunction "GND_SHIELD_69") (pintype "power_in"))
      (node (ref "U1") (pin "7") (pinfunction "GND_SHIELD_7") (pintype "power_in"))
      (node (ref "U1") (pin "72") (pinfunction "GND_SHIELD_72") (pintype "power_in"))
      (node (ref "U1") (pin "74") (pinfunction "GND_SHIELD_74") (pintype "power_in"))
      (node (ref "U1") (pin "75") (pinfunction "GND_SHIELD_75") (pintype "power_in"))
      (node (ref "U1") (pin "76") (pinfunction "GND_SHIELD_76") (pintype "power_in"))
      (node (ref "U1") (pin "77") (pinfunction "GND_SHIELD_77") (pintype "power_in"))
      (node (ref "U1") (pin "78") (pinfunction "GND_SHIELD_78") (pintype "power_in"))
      (node (ref "U1") (pin "79") (pinfunction "GND_SHIELD_79") (pintype "power_in"))
      (node (ref "U1") (pin "8") (pinfunction "GND_SHIELD_8") (pintype "power_in"))
      (node (ref "U1") (pin "80") (pinfunction "GND_SHIELD_80") (pintype "power_in"))
      (node (ref "U1") (pin "81") (pinfunction "GND_SHIELD_81") (pintype "power_in"))
      (node (ref "U1") (pin "82") (pinfunction "GND_SHIELD_82") (pintype "power_in"))
      (node (ref "U1") (pin "85") (pinfunction "GND_SHIELD_85") (pintype "power_in"))
      (node (ref "U1") (pin "9") (pinfunction "GND_SHIELD_9") (pintype "power_in"))
      (node (ref "U1") (pin "90") (pinfunction "GND_SHIELD_90") (pintype "power_in"))
      (node (ref "U1") (pin "94") (pinfunction "GND_SHIELD_94") (pintype "power_in"))
      (node (ref "U1") (pin "98") (pinfunction "GND_SHIELD_98") (pintype "power_in"))
      (node (ref "U10") (pin "3") (pinfunction "SDO/SAO_3") (pintype "bidirectional"))
      (node (ref "U10") (pin "5") (pinfunction "RES_5") (pintype "power_in"))
      (node (ref "U10") (pin "6") (pinfunction "GND_6") (pintype "power_in"))
      (node (ref "U10") (pin "7") (pinfunction "GND_7") (pintype "power_in"))
      (node (ref "U10") (pin "8") (pinfunction "GND_8") (pintype "power_in"))
      (node (ref "U2") (pin "12") (pinfunction "GND_12") (pintype "power_in"))
      (node (ref "U2") (pin "21") (pinfunction "GND_21") (pintype "power_in"))
      (node (ref "U2") (pin "3") (pinfunction "GND_3") (pintype "power_in"))
      (node (ref "U3") (pin "1") (pinfunction "GND_1") (pintype "power_in"))
      (node (ref "U3") (pin "3") (pinfunction "MODE_3") (pintype "input"))
      (node (ref "U4") (pin "2") (pinfunction "GND_2") (pintype "power_in"))
      (node (ref "U4") (pin "5") (pinfunction "GND_5") (pintype "power_in"))
      (node (ref "U5") (pin "4") (pinfunction "GND_4") (pintype "passive"))
      (node (ref "U5") (pin "9") (pinfunction "EPAD_9") (pintype "passive"))
      (node (ref "U6") (pin "4") (pinfunction "GND_4") (pintype "bidirectional"))
      (node (ref "U8") (pin "11") (pinfunction "VSS_11") (pintype "power_in"))
      (node (ref "U8") (pin "3") (pinfunction "CLKOE_3") (pintype "input"))
      (node (ref "U8") (pin "5") (pinfunction "VSS_5") (pintype "power_in"))
    )
    (net (code "15") (name "GPS") (class "Default")
      (node (ref "C12") (pin "1") (pinfunction "1_1") (pintype "passive"))
      (node (ref "U1") (pin "67") (pinfunction "GPS_67") (pintype "input"))
    )
    (net (code "16") (name "GPS_ANT") (class "Default")
      (node (ref "C12") (pin "2") (pinfunction "2_2") (pintype "passive"))
      (node (ref "J7") (pin "1") (pinfunction "SIG_1") (pintype "passive"))
      (node (ref "L4") (pin "2") (pinfunction "2_2") (pintype "passive"))
    )
    (net (code "17") (name "MODE{slash}WAKE") (class "Default")
      (node (ref "J3") (pin "3") (pinfunction "3_3") (pintype "bidirectional"))
      (node (ref "Q4") (pin "1") (pinfunction "G_1") (pintype "bidirectional"))
      (node (ref "R13") (pin "2") (pinfunction "2_2") (pintype "passive"))
      (node (ref "SW2") (pin "2") (pinfunction "2_2") (pintype "passive"))
      (node (ref "SW2") (pin "4") (pinfunction "2_4") (pintype "passive"))
    )
    (net (code "18") (name "Net-(D3-PadA)") (class "Default")
      (node (ref "D3") (pin "A") (pinfunction "A_A") (pintype "passive"))
      (node (ref "R11") (pin "1") (pinfunction "1_1") (pintype "passive"))
    )
    (net (code "19") (name "Net-(D4-PadA)") (class "Default")
      (node (ref "D4") (pin "A") (pinfunction "A_A") (pintype "passive"))
      (node (ref "R14") (pin "1") (pinfunction "1_1") (pintype "passive"))
    )
    (net (code "20") (name "Net-(J4-SIG)") (class "Default")
      (node (ref "J4") (pin "1") (pinfunction "SIG_1") (pintype "passive"))
      (node (ref "U1") (pin "61") (pinfunction "ANT_61") (pintype "bidirectional"))
    )
    (net (code "21") (name "Net-(J8-CC1)") (class "Default")
      (node (ref "J8") (pin "3") (pinfunction "CC1_3") (pintype "passive"))
      (node (ref "R6") (pin "1") (pinfunction "1_1") (pintype "passive"))
    )
    (net (code "22") (name "Net-(J8-CC2)") (class "Default")
      (node (ref "J8") (pin "9") (pinfunction "CC2_9") (pintype "passive"))
      (node (ref "R21") (pin "1") (pinfunction "1_1") (pintype "passive"))
    )
    (net (code "23") (name "Net-(JMP1-1)") (class "Default")
      (node (ref "JMP1") (pin "P$1") (pinfunction "1_P$1") (pintype "passive"))
      (node (ref "U10") (pin "12") (pinfunction "INT1_12") (pintype "output"))
    )
    (net (code "24") (name "Net-(JMP2-1)") (class "Default")
      (node (ref "JMP2") (pin "P$1") (pinfunction "1_P$1") (pintype "passive"))
      (node (ref "NTC1") (pin "2") (pinfunction "2_2") (pintype "passive"))
      (node (ref "U5") (pin "3") (pinfunction "TS_3") (pintype "input"))
    )
    (net (code "25") (name "Net-(JMP3-1)") (class "Default")
      (node (ref "JMP3") (pin "P$1") (pinfunction "1_P$1") (pintype "passive"))
      (node (ref "U10") (pin "11") (pinfunction "INT2_11") (pintype "output"))
    )
    (net (code "26") (name "Net-(L2-1)") (class "Default")
      (node (ref "L2") (pin "P$1") (pinfunction "1_P$1") (pintype "passive"))
      (node (ref "U3") (pin "7") (pinfunction "SW_7") (pintype "power_in"))
    )
    (net (code "27") (name "Net-(Q1-D)") (class "Default")
      (node (ref "D3") (pin "C") (pinfunction "C_C") (pintype "passive"))
      (node (ref "Q1") (pin "3") (pinfunction "D_3") (pintype "bidirectional"))
    )
    (net (code "28") (name "Net-(Q2A-D)") (class "Default")
      (node (ref "Q2") (pin "5") (pinfunction "G_5") (pintype "passive"))
      (node (ref "Q2") (pin "6") (pinfunction "D_6") (pintype "bidirectional"))
      (node (ref "R10") (pin "1") (pinfunction "1_1") (pintype "passive"))
    )
    (net (code "29") (name "Net-(Q2B-D)") (class "Default")
      (node (ref "Q2") (pin "3") (pinfunction "D_3") (pintype "passive"))
      (node (ref "R3") (pin "2") (pinfunction "2_2") (pintype "passive"))
    )
    (net (code "30") (name "Net-(U1-DEC0)") (class "Default")
      (node (ref "C9") (pin "1") (pinfunction "1_1") (pintype "passive"))
      (node (ref "U1") (pin "13") (pinfunction "DEC0_13") (pintype "power_in"))
    )
    (net (code "31") (name "Net-(U1-ENABLE)") (class "Default")
      (node (ref "R9") (pin "1") (pinfunction "1_1") (pintype "passive"))
      (node (ref "U1") (pin "101") (pinfunction "ENABLE_101") (pintype "input"))
    )
    (net (code "32") (name "Net-(U1-VDD1)") (class "Default")
      (node (ref "FB1") (pin "2") (pinfunction "2_2") (pintype "passive"))
      (node (ref "R9") (pin "2") (pinfunction "2_2") (pintype "passive"))
      (node (ref "U1") (pin "102") (pinfunction "VDD1_102") (pintype "power_in"))
    )
    (net (code "33") (name "Net-(U2-VBUS)") (class "Default")
      (node (ref "R15") (pin "1") (pinfunction "1_1") (pintype "passive"))
      (node (ref "R16") (pin "2") (pinfunction "2_2") (pintype "passive"))
      (node (ref "U2") (pin "8") (pinfunction "VBUS_8") (pintype "power_in"))
    )
    (net (code "34") (name "Net-(U2-~{RST})") (class "Default")
      (node (ref "R4") (pin "1") (pinfunction "1_1") (pintype "passive"))
      (node (ref "U2") (pin "9") (pinfunction "~{RST}_9") (pintype "input"))
    )
    (net (code "35") (name "Net-(U3-VSET)") (class "Default")
      (node (ref "R2") (pin "2") (pinfunction "2_2") (pintype "passive"))
      (node (ref "U3") (pin "5") (pinfunction "VSET_5") (pintype "input"))
    )
    (net (code "36") (name "Net-(U4-VOUT)") (class "Default")
      (node (ref "C19") (pin "1") (pinfunction "1_1") (pintype "passive"))
      (node (ref "L4") (pin "1") (pinfunction "1_1") (pintype "passive"))
      (node (ref "U4") (pin "4") (pinfunction "VOUT_4") (pintype "power_in"))
    )
    (net (code "37") (name "Net-(U5-ISET)") (class "Default")
      (node (ref "R12") (pin "2") (pinfunction "2_2") (pintype "passive"))
      (node (ref "U5") (pin "2") (pinfunction "ISET_2") (pintype "input"))
    )
    (net (code "38") (name "Net-(U5-VSET)") (class "Default")
      (node (ref "R7") (pin "2") (pinfunction "2_2") (pintype "passive"))
      (node (ref "U5") (pin "7") (pinfunction "VSET_7") (pintype "input"))
    )
    (net (code "39") (name "Net-(U8-OSCI)") (class "Default")
      (node (ref "U8") (pin "1") (pinfunction "OSCI_1") (pintype "input"))
      (node (ref "Y1") (pin "2") (pinfunction "2_2") (pintype "passive"))
    )
    (net (code "40") (name "Net-(U8-OSCO)") (class "Default")
      (node (ref "U8") (pin "2") (pinfunction "OSCO_2") (pintype "output"))
      (node (ref "Y1") (pin "1") (pinfunction "1_1") (pintype "passive"))
    )
    (net (code "41") (name "Net-(U10-CS)") (class "Default")
      (node (ref "R20") (pin "1") (pinfunction "1_1") (pintype "passive"))
      (node (ref "U10") (pin "2") (pinfunction "CS_2") (pintype "input"))
    )
    (net (code "42") (name "P0.00{slash}D4") (class "Default")
      (node (ref "J2") (pin "8") (pinfunction "8_8") (pintype "bidirectional"))
      (node (ref "U1") (pin "95") (pinfunction "P0.00_95") (pintype "bidirectional"))
    )
    (net (code "43") (name "P0.01{slash}D5") (class "Default")
      (node (ref "J2") (pin "7") (pinfunction "7_7") (pintype "bidirectional"))
      (node (ref "U1") (pin "96") (pinfunction "P0.01_96") (pintype "bidirectional"))
    )
    (net (code "44") (name "P0.02{slash}D6") (class "Default")
      (node (ref "J2") (pin "6") (pinfunction "6_6") (pintype "bidirectional"))
      (node (ref "U1") (pin "97") (pinfunction "P0.02_97") (pintype "bidirectional"))
    )
    (net (code "45") (name "P0.03{slash}D7") (class "Default")
      (node (ref "J2") (pin "5") (pinfunction "5_5") (pintype "bidirectional"))
      (node (ref "Q1") (pin "1") (pinfunction "G_1") (pintype "bidirectional"))
      (node (ref "R24") (pin "2") (pinfunction "2_2") (pintype "passive"))
      (node (ref "U1") (pin "99") (pinfunction "P0.03_99") (pintype "bidirectional"))
    )
    (net (code "46") (name "P0.04{slash}D8") (class "Default")
      (node (ref "J2") (pin "4") (pinfunction "4_4") (pintype "bidirectional"))
      (node (ref "JMP4") (pin "P$2") (pinfunction "2_P$2") (pintype "passive"))
      (node (ref "U1") (pin "100") (pinfunction "P0.04_100") (pintype "bidirectional"))
    )
    (net (code "47") (name "P0.05{slash}USB_UART_RX") (class "Default")
      (node (ref "U1") (pin "2") (pinfunction "P0.05_2") (pintype "bidirectional"))
      (node (ref "U2") (pin "18") (pinfunction "TXD_18") (pintype "output"))
    )
    (net (code "48") (name "P0.06{slash}USB_UART_TX") (class "Default")
      (node (ref "U1") (pin "3") (pinfunction "P0.06_3") (pintype "bidirectional"))
      (node (ref "U2") (pin "17") (pinfunction "RXD_17") (pintype "input"))
    )
    (net (code "49") (name "P0.12{slash}MD") (class "Default")
      (node (ref "Q4") (pin "3") (pinfunction "D_3") (pintype "bidirectional"))
      (node (ref "U1") (pin "20") (pinfunction "P0.12_20") (pintype "bidirectional"))
      (node (ref "U2") (pin "1") (pinfunction "GPIO.1/RS485_1") (pintype "bidirectional"))
    )
    (net (code "50") (name "P0.13{slash}A0") (class "Default")
      (node (ref "J3") (pin "5") (pinfunction "5_5") (pintype "bidirectional"))
      (node (ref "U1") (pin "23") (pinfunction "P0.13/AIN0_23") (pintype "bidirectional"))
    )
    (net (code "51") (name "P0.14{slash}A1") (class "Default")
      (node (ref "J3") (pin "6") (pinfunction "6_6") (pintype "bidirectional"))
      (node (ref "U1") (pin "24") (pinfunction "P0.14/AIN1_24") (pintype "bidirectional"))
    )
    (net (code "52") (name "P0.15{slash}A2") (class "Default")
      (node (ref "J3") (pin "7") (pinfunction "7_7") (pintype "bidirectional"))
      (node (ref "U1") (pin "25") (pinfunction "P0.15/AIN2_25") (pintype "bidirectional"))
    )
    (net (code "53") (name "P0.16{slash}A3") (class "Default")
      (node (ref "J3") (pin "8") (pinfunction "8_8") (pintype "bidirectional"))
      (node (ref "U1") (pin "26") (pinfunction "P0.16/AIN3_26") (pintype "bidirectional"))
    )
    (net (code "54") (name "P0.17{slash}A4") (class "Default")
      (node (ref "J3") (pin "9") (pinfunction "9_9") (pintype "bidirectional"))
      (node (ref "U1") (pin "28") (pinfunction "P0.17/AIN4_28") (pintype "bidirectional"))
    )
    (net (code "55") (name "P0.18{slash}A5") (class "Default")
      (node (ref "J3") (pin "10") (pinfunction "10_10") (pintype "bidirectional"))
      (node (ref "U1") (pin "29") (pinfunction "P0.18/AIN5_29") (pintype "bidirectional"))
    )
    (net (code "56") (name "P0.19{slash}SCK") (class "Default")
      (node (ref "J3") (pin "11") (pinfunction "11_11") (pintype "bidirectional"))
      (node (ref "U1") (pin "30") (pinfunction "P0.19/AIN6_30") (pintype "bidirectional"))
    )
    (net (code "57") (name "P0.20{slash}VBAT_MEAS") (class "Default")
      (node (ref "R3") (pin "1") (pinfunction "1_1") (pintype "passive"))
      (node (ref "R8") (pin "2") (pinfunction "2_2") (pintype "passive"))
      (node (ref "U1") (pin "35") (pinfunction "P0.20/AIN7_35") (pintype "bidirectional"))
    )
    (net (code "58") (name "P0.21{slash}COPI") (class "Default")
      (node (ref "J3") (pin "12") (pinfunction "12_12") (pintype "bidirectional"))
      (node (ref "U1") (pin "37") (pinfunction "P0.21/TRACECLK_37") (pintype "bidirectional"))
    )
    (net (code "59") (name "P0.22{slash}CIPO") (class "Default")
      (node (ref "J3") (pin "13") (pinfunction "13_13") (pintype "bidirectional"))
      (node (ref "U1") (pin "38") (pinfunction "P0.22/TRACEDATA0_38") (pintype "bidirectional"))
    )
    (net (code "60") (name "P0.23{slash}RX") (class "Default")
      (node (ref "J3") (pin "14") (pinfunction "14_14") (pintype "bidirectional"))
      (node (ref "U1") (pin "39") (pinfunction "P0.23/TRACEDATA1_39") (pintype "bidirectional"))
    )
    (net (code "61") (name "P0.24{slash}TX") (class "Default")
      (node (ref "J3") (pin "15") (pinfunction "15_15") (pintype "bidirectional"))
      (node (ref "U1") (pin "40") (pinfunction "P0.24/TRACEDATA2_40") (pintype "bidirectional"))
    )
    (net (code "62") (name "P0.25{slash}VBAT_MEAS_EN") (class "Default")
      (node (ref "Q2") (pin "2") (pinfunction "G_2") (pintype "bidirectional"))
      (node (ref "R5") (pin "2") (pinfunction "2_2") (pintype "passive"))
      (node (ref "U1") (pin "42") (pinfunction "P0.25/TRACEDATA3_42") (pintype "bidirectional"))
    )
    (net (code "63") (name "P0.26{slash}SDA") (class "Default")
      (node (ref "J2") (pin "12") (pinfunction "12_12") (pintype "bidirectional"))
      (node (ref "R17") (pin "1") (pinfunction "1_1") (pintype "passive"))
      (node (ref "U1") (pin "83") (pinfunction "P0.26_83") (pintype "bidirectional"))
      (node (ref "U10") (pin "4") (pinfunction "SDA/SDI/SDO_4") (pintype "bidirectional"))
      (node (ref "U8") (pin "6") (pinfunction "SDA_6") (pintype "bidirectional"))
    )
    (net (code "64") (name "P0.27{slash}SCL") (class "Default")
      (node (ref "J2") (pin "11") (pinfunction "11_11") (pintype "bidirectional"))
      (node (ref "R18") (pin "1") (pinfunction "1_1") (pintype "passive"))
      (node (ref "U1") (pin "84") (pinfunction "P0.27_84") (pintype "bidirectional"))
      (node (ref "U10") (pin "1") (pinfunction "SCL/SPC_1") (pintype "bidirectional"))
      (node (ref "U8") (pin "7") (pinfunction "SCL_7") (pintype "input"))
    )
    (net (code "65") (name "P0.29{slash}D2") (class "Default")
      (node (ref "J2") (pin "10") (pinfunction "10_10") (pintype "bidirectional"))
      (node (ref "JMP3") (pin "P$2") (pinfunction "2_P$2") (pintype "passive"))
      (node (ref "U1") (pin "87") (pinfunction "P0.29_87") (pintype "bidirectional"))
    )
    (net (code "66") (name "P0.30{slash}D3") (class "Default")
      (node (ref "J2") (pin "9") (pinfunction "9_9") (pintype "bidirectional"))
      (node (ref "JMP1") (pin "P$2") (pinfunction "2_P$2") (pintype "passive"))
      (node (ref "U1") (pin "88") (pinfunction "P0.30_88") (pintype "bidirectional"))
    )
    (net (code "67") (name "P0.31") (class "Default")
      (node (ref "J3") (pin "16") (pinfunction "16_16") (pintype "bidirectional"))
      (node (ref "U1") (pin "89") (pinfunction "P0.31_89") (pintype "bidirectional"))
    )
    (net (code "68") (name "RTC_INT") (class "Default")
      (node (ref "JMP4") (pin "P$1") (pinfunction "1_P$1") (pintype "passive"))
      (node (ref "U8") (pin "4") (pinfunction "~{INT}_4") (pintype "output"))
    )
    (net (code "69") (name "SIM_CLK") (class "Default")
      (node (ref "J5") (pin "S3") (pinfunction "CLK_S3") (pintype "input"))
      (node (ref "TP3") (pin "TP") (pinfunction "TP_TP") (pintype "input"))
      (node (ref "U1") (pin "46") (pinfunction "SIM_CLK_46") (pintype "bidirectional"))
    )
    (net (code "70") (name "SIM_IO") (class "Default")
      (node (ref "J5") (pin "S6") (pinfunction "I/O_S6") (pintype "bidirectional"))
      (node (ref "TP6") (pin "TP") (pinfunction "TP_TP") (pintype "input"))
      (node (ref "U1") (pin "48") (pinfunction "SIM_IO_48") (pintype "bidirectional"))
    )
    (net (code "71") (name "SIM_RST") (class "Default")
      (node (ref "J5") (pin "S2") (pinfunction "RST_S2") (pintype "input"))
      (node (ref "TP4") (pin "TP") (pinfunction "TP_TP") (pintype "input"))
      (node (ref "U1") (pin "43") (pinfunction "SIM_RST_43") (pintype "bidirectional"))
    )
    (net (code "72") (name "SIM_VCC") (class "Default")
      (node (ref "J5") (pin "S1") (pinfunction "VCC_S1") (pintype "power_in"))
      (node (ref "TP5") (pin "TP") (pinfunction "TP_TP") (pintype "input"))
      (node (ref "U1") (pin "49") (pinfunction "SIM_1V8_49") (pintype "power_in"))
    )
    (net (code "73") (name "SWCLK") (class "Default")
      (node (ref "J9") (pin "4") (pinfunction "SWCLK_4") (pintype "bidirectional"))
      (node (ref "TP2") (pin "TP") (pinfunction "TP_TP") (pintype "input"))
      (node (ref "U1") (pin "33") (pinfunction "SWDCLK_33") (pintype "input"))
    )
    (net (code "74") (name "SWDIO") (class "Default")
      (node (ref "J9") (pin "2") (pinfunction "SWDIO_2") (pintype "bidirectional"))
      (node (ref "TP1") (pin "TP") (pinfunction "TP_TP") (pintype "input"))
      (node (ref "U1") (pin "34") (pinfunction "SWDIO_34") (pintype "bidirectional"))
    )
    (net (code "75") (name "VBAT") (class "Default")
      (node (ref "C6") (pin "1") (pinfunction "1_1") (pintype "passive"))
      (node (ref "J2") (pin "1") (pinfunction "1_1") (pintype "bidirectional"))
      (node (ref "J6") (pin "1") (pinfunction "1_1") (pintype "passive"))
      (node (ref "Q2") (pin "4") (pinfunction "S_4") (pintype "passive"))
      (node (ref "Q3") (pin "3") (pinfunction "D_3") (pintype "passive"))
      (node (ref "R10") (pin "2") (pinfunction "2_2") (pintype "passive"))
      (node (ref "U5") (pin "8") (pinfunction "OUT_8") (pintype "output"))
    )
    (net (code "76") (name "VBUS") (class "Default")
      (node (ref "C11") (pin "1") (pinfunction "1_1") (pintype "passive"))
      (node (ref "C13") (pin "1") (pinfunction "1_1") (pintype "passive"))
      (node (ref "C14") (pin "1") (pinfunction "1_1") (pintype "passive"))
      (node (ref "D1") (pin "2") (pinfunction "1_2") (pintype "passive"))
      (node (ref "J2") (pin "3") (pinfunction "3_3") (pintype "bidirectional"))
      (node (ref "J8") (pin "11") (pinfunction "VBUS_11") (pintype "power_in"))
      (node (ref "J8") (pin "2") (pinfunction "VBUS_2") (pintype "power_in"))
      (node (ref "Q3") (pin "1") (pinfunction "G_1") (pintype "passive"))
      (node (ref "R14") (pin "2") (pinfunction "2_2") (pintype "passive"))
      (node (ref "R15") (pin "2") (pinfunction "2_2") (pintype "passive"))
      (node (ref "R4") (pin "2") (pinfunction "2_2") (pintype "passive"))
      (node (ref "U2") (pin "7") (pinfunction "VREGIN_7") (pintype "power_in"))
      (node (ref "U5") (pin "1") (pinfunction "IN_1") (pintype "power_in"))
    )
    (net (code "77") (name "VIO") (class "Default")
      (node (ref "U1") (pin "57") (pinfunction "VIO_57") (pintype "power_in"))
    )
    (net (code "78") (name "VPP") (class "Default")
      (node (ref "J5") (pin "S5") (pinfunction "VPP_S5") (pintype "power_in"))
    )
    (net (code "79") (name "VSYS") (class "Default")
      (node (ref "C5") (pin "1") (pinfunction "1_1") (pintype "passive"))
      (node (ref "D1") (pin "1") (pinfunction "2_1") (pintype "passive"))
      (node (ref "Q3") (pin "2") (pinfunction "S_2") (pintype "passive"))
      (node (ref "R19") (pin "1") (pinfunction "1_1") (pintype "passive"))
      (node (ref "SW2") (pin "1") (pinfunction "1_1") (pintype "passive"))
      (node (ref "SW2") (pin "3") (pinfunction "1_3") (pintype "passive"))
      (node (ref "U3") (pin "2") (pinfunction "VIN_2") (pintype "power_in"))
    )
    (net (code "80") (name "unconnected-(J8-SBU1-Pad10)") (class "Default")
      (node (ref "J8") (pin "10") (pinfunction "SBU1_10") (pintype "passive"))
    )
    (net (code "81") (name "unconnected-(J8-SBU2-Pad4)") (class "Default")
      (node (ref "J8") (pin "4") (pinfunction "SBU2_4") (pintype "passive"))
    )
    (net (code "82") (name "unconnected-(J9-SWO-Pad6)") (class "Default")
      (node (ref "J9") (pin "6") (pinfunction "SWO_6") (pintype "bidirectional"))
    )
    (net (code "83") (name "unconnected-(J9-~{RST}-Pad3)") (class "Default")
      (node (ref "J9") (pin "3") (pinfunction "~{RST}_3") (pintype "bidirectional"))
    )
    (net (code "84") (name "unconnected-(U1-AUX-Pad64)") (class "Default")
      (node (ref "U1") (pin "64") (pinfunction "AUX_64") (pintype "output"))
    )
    (net (code "85") (name "unconnected-(U1-COEX1-Pad92)") (class "Default")
      (node (ref "U1") (pin "92") (pinfunction "COEX1_92") (pintype "bidirectional"))
    )
    (net (code "86") (name "unconnected-(U1-COEX2-Pad91)") (class "Default")
      (node (ref "U1") (pin "91") (pinfunction "COEX2_91") (pintype "bidirectional"))
    )
    (net (code "87") (name "unconnected-(U1-MAGPIO0-Pad55)") (class "Default")
      (node (ref "U1") (pin "55") (pinfunction "MAGPIO0_55") (pintype "bidirectional"))
    )
    (net (code "88") (name "unconnected-(U1-MAGPIO1-Pad54)") (class "Default")
      (node (ref "U1") (pin "54") (pinfunction "MAGPIO1_54") (pintype "bidirectional"))
    )
    (net (code "89") (name "unconnected-(U1-MAGPIO2-Pad53)") (class "Default")
      (node (ref "U1") (pin "53") (pinfunction "MAGPIO2_53") (pintype "bidirectional"))
    )
    (net (code "90") (name "unconnected-(U1-SCLK-Pad58)") (class "Default")
      (node (ref "U1") (pin "58") (pinfunction "SCLK_58") (pintype "bidirectional"))
    )
    (net (code "91") (name "unconnected-(U1-SDATA-Pad59)") (class "Default")
      (node (ref "U1") (pin "59") (pinfunction "SDATA_59") (pintype "bidirectional"))
    )
    (net (code "92") (name "unconnected-(U1-SIM_DET-Pad45)") (class "Default")
      (node (ref "U1") (pin "45") (pinfunction "SIM_DET_45") (pintype "bidirectional"))
    )
    (net (code "93") (name "unconnected-(U2-CTS-Pad15)") (class "Default")
      (node (ref "U2") (pin "15") (pinfunction "CTS_15") (pintype "input"))
    )
    (net (code "94") (name "unconnected-(U2-GPIO.2{slash}TXT-Pad20)") (class "Default")
      (node (ref "U2") (pin "20") (pinfunction "GPIO.2/TXT_20") (pintype "bidirectional"))
    )
    (net (code "95") (name "unconnected-(U2-GPIO.3{slash}RXT-Pad19)") (class "Default")
      (node (ref "U2") (pin "19") (pinfunction "GPIO.3/RXT_19") (pintype "bidirectional"))
    )
    (net (code "96") (name "unconnected-(U2-RTS-Pad16)") (class "Default")
      (node (ref "U2") (pin "16") (pinfunction "RTS_16") (pintype "output"))
    )
    (net (code "97") (name "unconnected-(U2-SUSPEND-Pad14)") (class "Default")
      (node (ref "U2") (pin "14") (pinfunction "SUSPEND_14") (pintype "output"))
    )
    (net (code "98") (name "unconnected-(U2-WAKEUP-Pad13)") (class "Default")
      (node (ref "U2") (pin "13") (pinfunction "WAKEUP_13") (pintype "input"))
    )
    (net (code "99") (name "unconnected-(U2-~{SUSPEND}-Pad11)") (class "Default")
      (node (ref "U2") (pin "11") (pinfunction "~{SUSPEND}_11") (pintype "output"))
    )
    (net (code "100") (name "unconnected-(U3-STOP-Pad6)") (class "Default")
      (node (ref "U3") (pin "6") (pinfunction "STOP_6") (pintype "input"))
    )
    (net (code "101") (name "unconnected-(U5-PG-Pad6)") (class "Default")
      (node (ref "U5") (pin "6") (pinfunction "PG_6") (pintype "output"))
    )
    (net (code "102") (name "unconnected-(U8-CLKOUT-Pad9)") (class "Default")
      (node (ref "U8") (pin "9") (pinfunction "CLKOUT_9") (pintype "output"))
    )
    (net (code "103") (name "~{RESET}") (class "Default")
      (node (ref "J3") (pin "1") (pinfunction "1_1") (pintype "bidirectional"))
      (node (ref "SW1") (pin "1") (pinfunction "1_1") (pintype "passive"))
      (node (ref "SW1") (pin "3") (pinfunction "1_3") (pintype "passive"))
      (node (ref "U1") (pin "32") (pinfunction "NRESET_32") (pintype "input"))
      (node (ref "U2") (pin "2") (pinfunction "GPIO.0/CLK_2") (pintype "bidirectional"))
    )
  )
)
